# Sheet1.net
KiCad netlist of a schematic drawn in Altium Designer
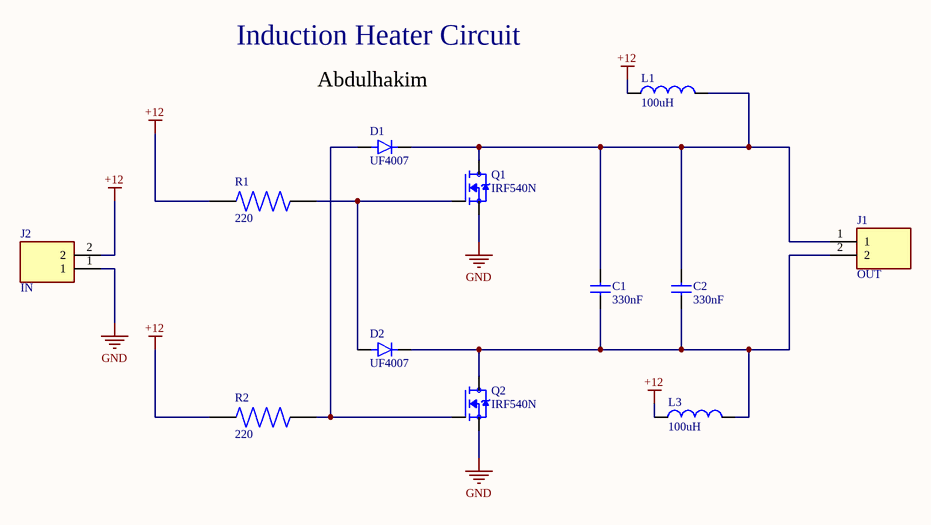
[diagram p0: Sheet1.SchDoc]

(export (version "E")
  (design (tool "Eeschema 10.0.6"))
  (components
    (comp (ref "C1")
      (value "330nF")
      (footprint "WCAP-FTX2_P15L18W8.5H14.5_CS")
      (description "WCAP-FTX2 Film Capacitor 330nF 275Vac ¦ Wurth Electronics 890324025034CS")
      (fields (field (name "MF") "WÃ¼rth Elektronik") (field (name "MP") "890324025034CS"))
      (libsource (lib "cap bank") (part "WCAP-FTX2_P15_CS"))
    )
    (comp (ref "C2")
      (value "330nF")
      (footprint "WCAP-FTX2_P15L18W8.5H14.5_CS")
      (description "WCAP-FTX2 Film Capacitor 330nF 275Vac ¦ Wurth Electronics 890324025034CS")
      (fields (field (name "MF") "WÃ¼rth Elektronik") (field (name "MP") "890324025034CS"))
      (libsource (lib "cap bank") (part "WCAP-FTX2_P15_CS"))
    )
    (comp (ref "D1")
      (value "UF4007")
      (footprint "DIOAD1036W78L470D235")
      (description "UF4007 Series 1 A 1000 V 75 ns Through Hole Fast Rectifier - DO-41")
      (fields (field (name "MF") "Fairchild Semiconductor") (field (name "MP") "UF4007."))
      (libsource (lib "UF4007") (part "UF4007"))
    )
    (comp (ref "D2")
      (value "UF4007")
      (footprint "DIOAD1036W78L470D235")
      (description "UF4007 Series 1 A 1000 V 75 ns Through Hole Fast Rectifier - DO-41")
      (fields (field (name "MF") "Fairchild Semiconductor") (field (name "MP") "UF4007."))
      (libsource (lib "UF4007") (part "UF4007"))
    )
    (comp (ref "J1")
      (value "OUT")
      (footprint "CUI_TB007-508-02BE")
      (description "2~24 Poles, Screw Type, Horizontal, 5.08 Pitch, 24~12 (AWG), Terminal Block Connector")
      (fields (field (name "MF") "Same Sky") (field (name "MP") "TB007-508-02BE"))
      (libsource (lib "") (part "TB007-508-02BE_1"))
    )
    (comp (ref "J2")
      (value "IN")
      (footprint "CUI_TB007-508-02BE")
      (description "2~24 Poles, Screw Type, Horizontal, 5.08 Pitch, 24~12 (AWG), Terminal Block Connector")
      (fields (field (name "MF") "Same Sky") (field (name "MP") "TB007-508-02BE"))
      (libsource (lib "TB007-508-02BE") (part "TB007-508-02BE"))
    )
    (comp (ref "L1")
      (value "100uH")
      (footprint "WE-SI_744132")
      (description "L = 49 ÂµH ; IR = 5.8 A; Isat = 2.2 A; RDC = 0.05 â„¦")
      (fields (field (name "MF") "Wurth Elektronik") (field (name "MP") "744132"))
      (libsource (lib "WE-SI") (part "WE-SI"))
    )
    (comp (ref "L3")
      (value "100uH")
      (footprint "WE-SI_744132")
      (description "L = 49 ÂµH ; IR = 5.8 A; Isat = 2.2 A; RDC = 0.05 â„¦")
      (fields (field (name "MF") "Wurth Elektronik") (field (name "MP") "744132"))
      (libsource (lib "WE-SI") (part "WE-SI"))
    )
    (comp (ref "Q1")
      (value "IRF540N")
      (footprint "TO254P1054X469X1930-3")
      (description "Transistor NPN MOS IRF540/IRF540N INTERNATIONAL RECTIFIER Ampere=28 V=100 TO220")
      (fields (field (name "MF") "Infineon Technologies"))
      (libsource (lib "IRF540Nsinked") (part "IRF540N"))
    )
    (comp (ref "Q2")
      (value "IRF540N")
      (footprint "TO254P1054X469X1930-3")
      (description "Transistor NPN MOS IRF540/IRF540N INTERNATIONAL RECTIFIER Ampere=28 V=100 TO220")
      (fields (field (name "MF") "Infineon Technologies"))
      (libsource (lib "IRF540Nsinked") (part "IRF540N"))
    )
    (comp (ref "R1")
      (value "220")
      (footprint "RESC6331X75N")
      (fields (field (name "MF") "Bourns") (field (name "MP") "CR2512-JW-221ELF"))
      (libsource (lib "220ohm1wat") (part "CR2512-JW-221ELF"))
    )
    (comp (ref "R2")
      (value "220")
      (footprint "RESC6331X75N")
      (fields (field (name "MF") "Bourns") (field (name "MP") "CR2512-JW-221ELF"))
      (libsource (lib "220ohm1wat") (part "CR2512-JW-221ELF"))
    )
  )
  (nets
    (net (code "1") (name "+12") (class "Default")
      (node (ref "J2") (pin "2") (pinfunction "2_2") (pintype "passive"))
      (node (ref "L1") (pin "1") (pinfunction "1_1") (pintype "passive"))
      (node (ref "L3") (pin "1") (pinfunction "1_1") (pintype "passive"))
      (node (ref "R1") (pin "1") (pinfunction "1_1") (pintype "passive"))
      (node (ref "R2") (pin "1") (pinfunction "1_1") (pintype "passive"))
    )
    (net (code "2") (name "GND") (class "Default")
      (node (ref "J2") (pin "1") (pinfunction "1_1") (pintype "passive"))
      (node (ref "Q1") (pin "3") (pinfunction "S_3") (pintype "passive"))
      (node (ref "Q2") (pin "3") (pinfunction "S_3") (pintype "passive"))
    )
    (net (code "3") (name "Net-(D1-K)") (class "Default")
      (node (ref "C1") (pin "2") (pinfunction "2_2") (pintype "passive"))
      (node (ref "C2") (pin "2") (pinfunction "2_2") (pintype "passive"))
      (node (ref "D1") (pin "C") (pinfunction "K_C") (pintype "passive"))
      (node (ref "J1") (pin "1") (pinfunction "1_1") (pintype "passive"))
      (node (ref "L1") (pin "2") (pinfunction "2_2") (pintype "passive"))
      (node (ref "Q1") (pin "2") (pinfunction "D_2") (pintype "passive"))
    )
    (net (code "4") (name "Net-(D2-K)") (class "Default")
      (node (ref "C1") (pin "1") (pinfunction "1_1") (pintype "passive"))
      (node (ref "C2") (pin "1") (pinfunction "1_1") (pintype "passive"))
      (node (ref "D2") (pin "C") (pinfunction "K_C") (pintype "passive"))
      (node (ref "J1") (pin "2") (pinfunction "2_2") (pintype "passive"))
      (node (ref "L3") (pin "2") (pinfunction "2_2") (pintype "passive"))
      (node (ref "Q2") (pin "2") (pinfunction "D_2") (pintype "passive"))
    )
    (net (code "5") (name "Net-(Q1-G)") (class "Default")
      (node (ref "D2") (pin "A") (pinfunction "A_A") (pintype "passive"))
      (node (ref "Q1") (pin "1") (pinfunction "G_1") (pintype "passive"))
      (node (ref "R1") (pin "2") (pinfunction "2_2") (pintype "passive"))
    )
    (net (code "6") (name "Net-(Q2-G)") (class "Default")
      (node (ref "D1") (pin "A") (pinfunction "A_A") (pintype "passive"))
      (node (ref "Q2") (pin "1") (pinfunction "G_1") (pintype "passive"))
      (node (ref "R2") (pin "2") (pinfunction "2_2") (pintype "passive"))
    )
  )
)
